# PokerFace.net
KiCad netlist of a schematic drawn in Altium Designer
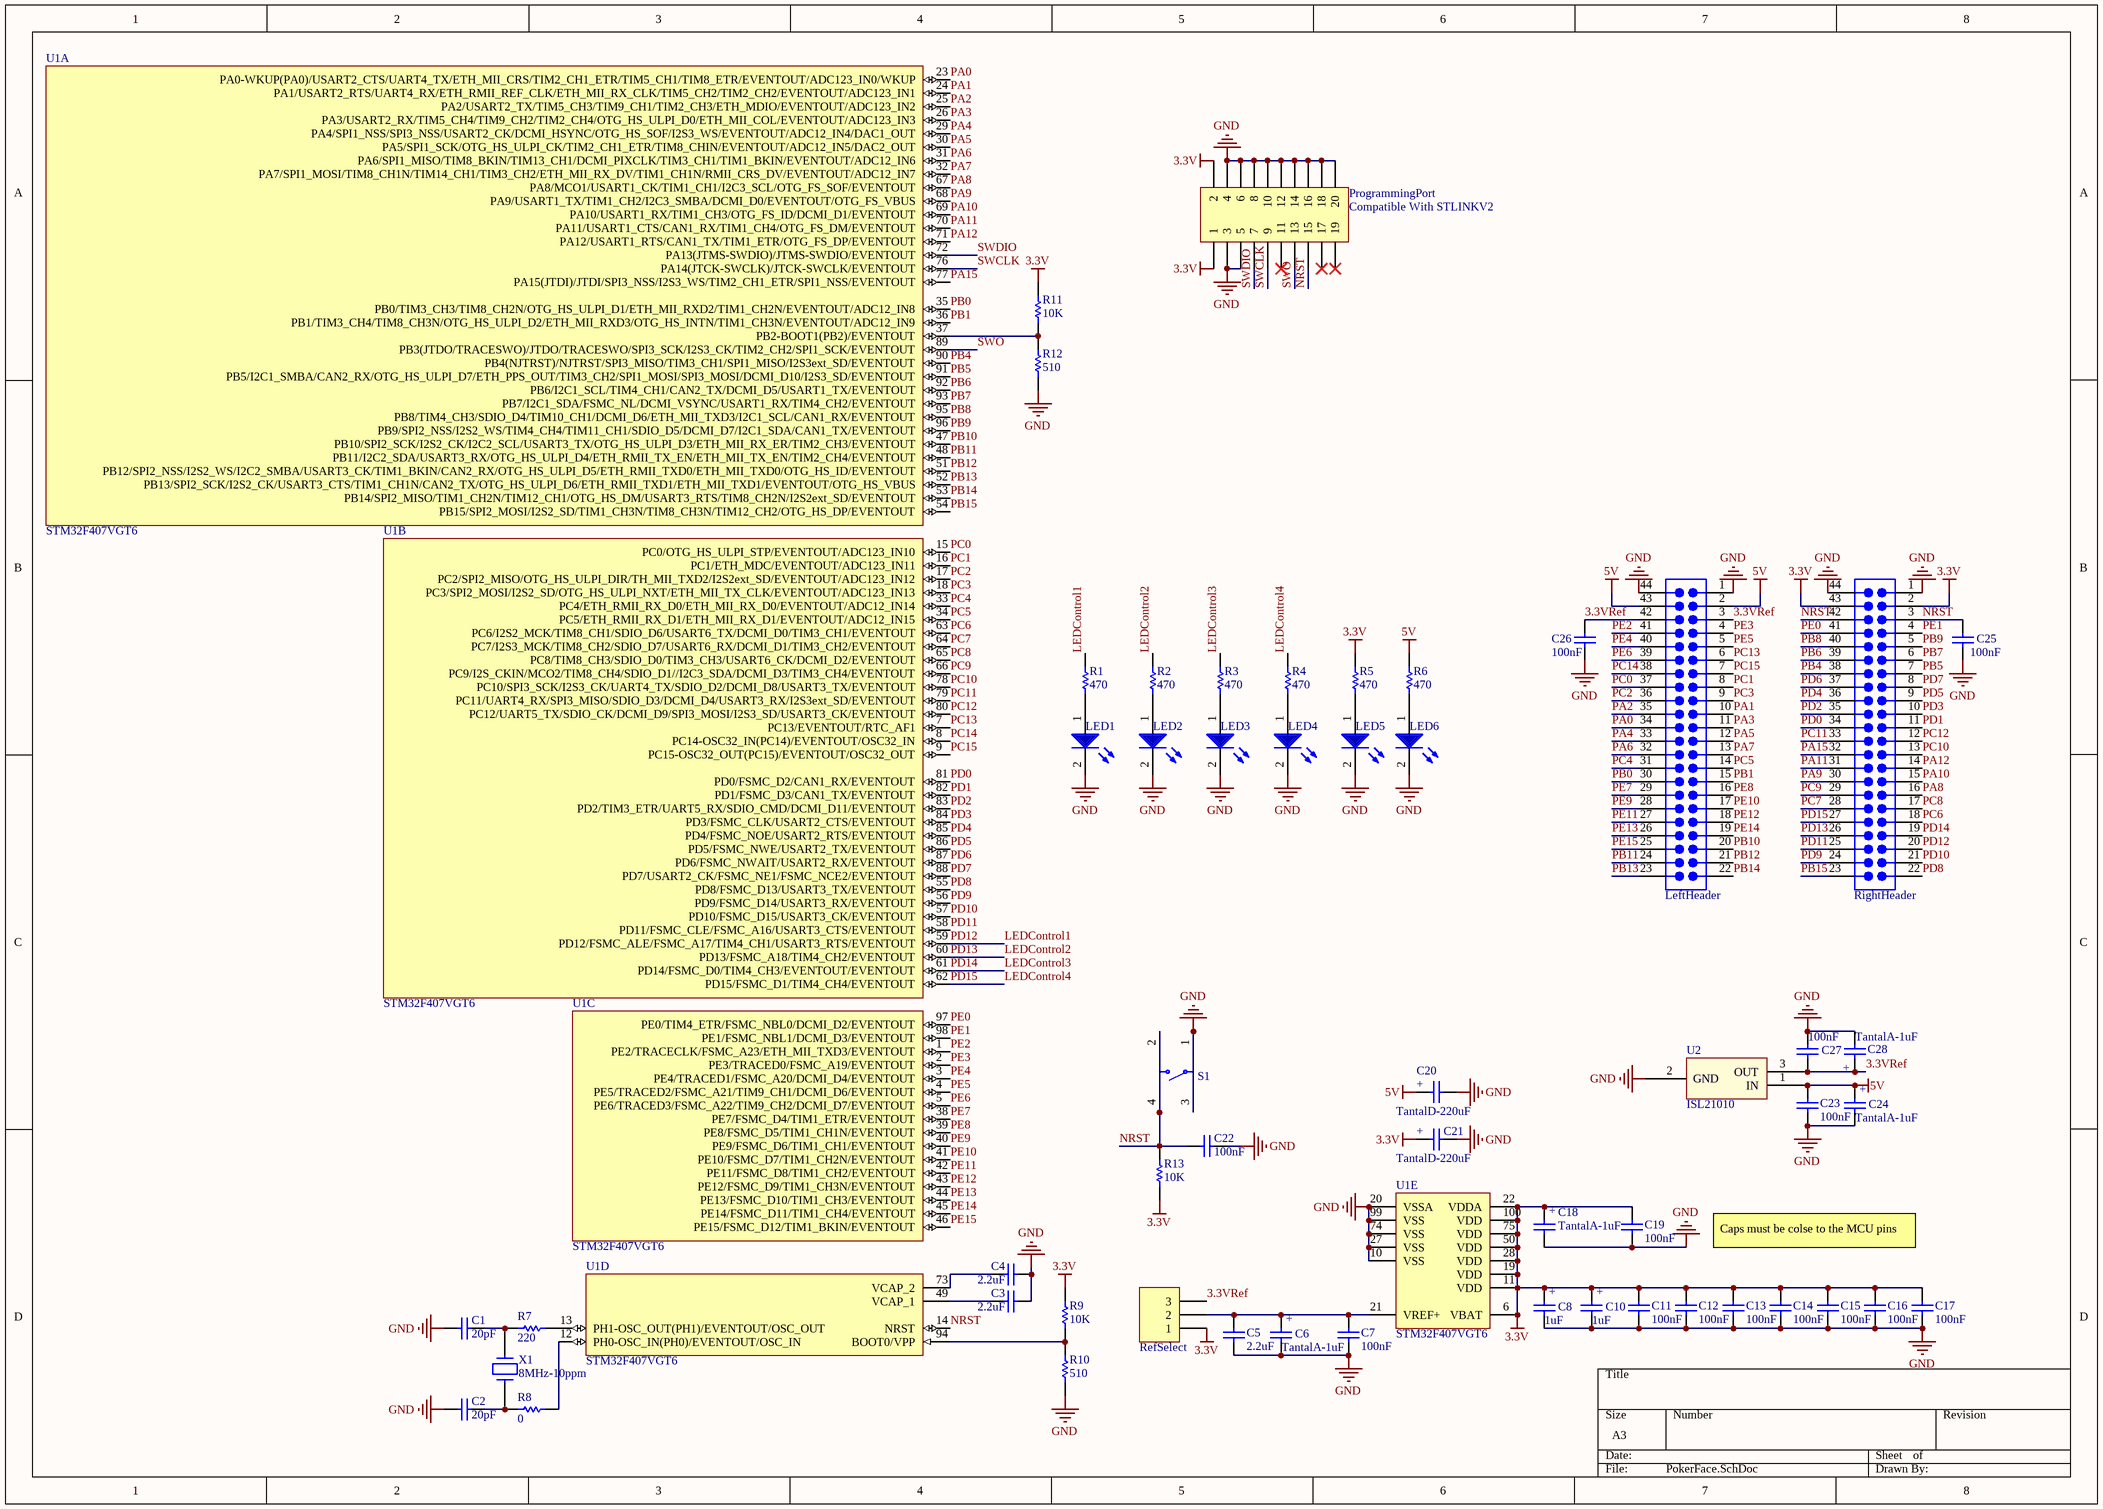
[diagram p0: PokerFace.SchDoc]

(export (version "E")
  (design (tool "Eeschema 10.0.6"))
  (components
    (comp (ref "C1")
      (value "20pF")
      (footprint "SMD 805 CAP")
      (libsource (lib "Aryalib") (part "CAP without Pole"))
    )
    (comp (ref "C2")
      (value "20pF")
      (footprint "SMD 805 CAP")
      (libsource (lib "Aryalib") (part "CAP without Pole"))
    )
    (comp (ref "C3")
      (value "2.2uF")
      (footprint "SMD 805 CAP")
      (libsource (lib "Aryalib") (part "CAP without Pole"))
    )
    (comp (ref "C4")
      (value "2.2uF")
      (footprint "SMD 805 CAP")
      (libsource (lib "Aryalib") (part "CAP without Pole"))
    )
    (comp (ref "C5")
      (value "2.2uF")
      (footprint "SMD 805 CAP")
      (libsource (lib "Aryalib") (part "CAP without Pole"))
    )
    (comp (ref "C6")
      (value "TantalA-1uF")
      (footprint "MY_CAP_SMD-A")
      (description "3.2X1.6MM")
      (libsource (lib "AMINLIB") (part "CAP_TANTAL_A"))
    )
    (comp (ref "C7")
      (value "100nF")
      (footprint "SMD 805 CAP")
      (libsource (lib "Aryalib") (part "CAP without Pole"))
    )
    (comp (ref "C8")
      (value "1uF")
      (footprint "MY_CAP_SMD-A")
      (description "3.2X1.6MM")
      (libsource (lib "AMINLIB") (part "CAP_TANTAL_A"))
    )
    (comp (ref "C10")
      (value "1uF")
      (footprint "MY_CAP_SMD-A")
      (description "3.2X1.6MM")
      (libsource (lib "AMINLIB") (part "CAP_TANTAL_A"))
    )
    (comp (ref "C11")
      (value "100nF")
      (footprint "SMD 805 CAP")
      (libsource (lib "Aryalib") (part "CAP without Pole"))
    )
    (comp (ref "C12")
      (value "100nF")
      (footprint "SMD 805 CAP")
      (libsource (lib "Aryalib") (part "CAP without Pole"))
    )
    (comp (ref "C13")
      (value "100nF")
      (footprint "SMD 805 CAP")
      (libsource (lib "Aryalib") (part "CAP without Pole"))
    )
    (comp (ref "C14")
      (value "100nF")
      (footprint "SMD 805 CAP")
      (libsource (lib "Aryalib") (part "CAP without Pole"))
    )
    (comp (ref "C15")
      (value "100nF")
      (footprint "SMD 805 CAP")
      (libsource (lib "Aryalib") (part "CAP without Pole"))
    )
    (comp (ref "C16")
      (value "100nF")
      (footprint "SMD 805 CAP")
      (libsource (lib "Aryalib") (part "CAP without Pole"))
    )
    (comp (ref "C17")
      (value "100nF")
      (footprint "SMD 805 CAP")
      (libsource (lib "Aryalib") (part "CAP without Pole"))
    )
    (comp (ref "C18")
      (value "TantalA-1uF")
      (footprint "MY_CAP_SMD-A")
      (description "3.2X1.6MM")
      (libsource (lib "AMINLIB") (part "CAP_TANTAL_A"))
    )
    (comp (ref "C19")
      (value "100nF")
      (footprint "SMD 805 CAP")
      (libsource (lib "Aryalib") (part "CAP without Pole"))
    )
    (comp (ref "C20")
      (value "TantalD-220uF")
      (footprint "MY_CAP_SMD-D")
      (description "7.3X4.3MM")
      (libsource (lib "AMINLIB") (part "CAP_TANTAL_D"))
    )
    (comp (ref "C21")
      (value "TantalD-220uF")
      (footprint "MY_CAP_SMD-D")
      (description "7.3X4.3MM")
      (libsource (lib "AMINLIB") (part "CAP_TANTAL_D"))
    )
    (comp (ref "C22")
      (value "100nF")
      (footprint "SMD 805 CAP")
      (libsource (lib "Aryalib") (part "CAP without Pole"))
    )
    (comp (ref "C23")
      (value "100nF")
      (footprint "SMD 805 CAP")
      (libsource (lib "Aryalib") (part "CAP without Pole"))
    )
    (comp (ref "C24")
      (value "TantalA-1uF")
      (footprint "MY_CAP_SMD-A")
      (description "3.2X1.6MM")
      (libsource (lib "AMINLIB") (part "CAP_TANTAL_A"))
    )
    (comp (ref "C25")
      (value "100nF")
      (footprint "SMD 805 CAP")
      (libsource (lib "Aryalib") (part "CAP without Pole"))
    )
    (comp (ref "C26")
      (value "100nF")
      (footprint "SMD 805 CAP")
      (libsource (lib "Aryalib") (part "CAP without Pole"))
    )
    (comp (ref "C27")
      (value "100nF")
      (footprint "SMD 805 CAP")
      (libsource (lib "Aryalib") (part "CAP without Pole"))
    )
    (comp (ref "C28")
      (value "TantalA-1uF")
      (footprint "MY_CAP_SMD-A")
      (description "3.2X1.6MM")
      (libsource (lib "AMINLIB") (part "CAP_TANTAL_A"))
    )
    (comp (ref "LED1")
      (value "150080BS75000")
      (footprint "LED_0805_Blue")
      (description "SMD mono-color Chip LED, WL-SMCW, Blue")
      (fields
        (field (name "MANUFACTURER") "W黵th Elektronik eiSos GmbH")
        (field (name "CREATED BY") "Christin Otto")
      )
      (libsource (lib "WL-SMCW_rev15b") (part "WL-SMCW 0805  150080BS75000"))
    )
    (comp (ref "LED2")
      (value "150080BS75000")
      (footprint "LED_0805_Blue")
      (description "SMD mono-color Chip LED, WL-SMCW, Blue")
      (fields
        (field (name "MANUFACTURER") "W黵th Elektronik eiSos GmbH")
        (field (name "CREATED BY") "Christin Otto")
      )
      (libsource (lib "WL-SMCW_rev15b") (part "WL-SMCW 0805  150080BS75000"))
    )
    (comp (ref "LED3")
      (value "150080BS75000")
      (footprint "LED_0805_Blue")
      (description "SMD mono-color Chip LED, WL-SMCW, Blue")
      (fields
        (field (name "MANUFACTURER") "W黵th Elektronik eiSos GmbH")
        (field (name "CREATED BY") "Christin Otto")
      )
      (libsource (lib "WL-SMCW_rev15b") (part "WL-SMCW 0805  150080BS75000"))
    )
    (comp (ref "LED4")
      (value "150080BS75000")
      (footprint "LED_0805_Blue")
      (description "SMD mono-color Chip LED, WL-SMCW, Blue")
      (fields
        (field (name "MANUFACTURER") "W黵th Elektronik eiSos GmbH")
        (field (name "CREATED BY") "Christin Otto")
      )
      (libsource (lib "WL-SMCW_rev15b") (part "WL-SMCW 0805  150080BS75000"))
    )
    (comp (ref "LED5")
      (value "150080BS75000")
      (footprint "LED_0805_Blue")
      (description "SMD mono-color Chip LED, WL-SMCW, Blue")
      (fields
        (field (name "MANUFACTURER") "W黵th Elektronik eiSos GmbH")
        (field (name "CREATED BY") "Christin Otto")
      )
      (libsource (lib "WL-SMCW_rev15b") (part "WL-SMCW 0805  150080BS75000"))
    )
    (comp (ref "LED6")
      (value "150080BS75000")
      (footprint "LED_0805_Blue")
      (description "SMD mono-color Chip LED, WL-SMCW, Blue")
      (fields
        (field (name "MANUFACTURER") "W黵th Elektronik eiSos GmbH")
        (field (name "CREATED BY") "Christin Otto")
      )
      (libsource (lib "WL-SMCW_rev15b") (part "WL-SMCW 0805  150080BS75000"))
    )
    (comp (ref "LeftHeader")
      (value "WE-2.54 mm Pin Header & Jumper 61304421121")
      (footprint "61304421121")
      (description "WR-PHD 2.54 mm Dual Pin Header")
      (fields
        (field (name "MANUFACTURER") "Würth Elektronik eiSos GmbH")
        (field (name "PARTNO") "61304421121")
        (field (name "CREATED BY") "Karrer Zheng")
      )
      (libsource (lib "WE_WR-PHD_Pin Header_2.54mm_rev15c") (part "WE-2.54 mm Pin Header & Jumper 61304421121"))
    )
    (comp (ref "ProgrammingPort")
      (value "Compatible With STLINKV2")
      (footprint "61202021621")
      (description "WR-BHD 2.54mm Male Box Header")
      (fields
        (field (name "MANUFACTURER") "Würth Elektronik eiSos GmbH")
        (field (name "PARTNO") "61202021621")
        (field (name "CREATED BY") "Karrer Zheng")
      )
      (libsource (lib "WE_WR-BHD_Box Header_2.54mm_rev15b") (part "WE-2,54mm_Box Header 61202021621"))
    )
    (comp (ref "R1") (value "470") (footprint "SMD 805") (libsource (lib "Aryalib") (part "Resistor")))
    (comp (ref "R2") (value "470") (footprint "SMD 805") (libsource (lib "Aryalib") (part "Resistor")))
    (comp (ref "R3") (value "470") (footprint "SMD 805") (libsource (lib "Aryalib") (part "Resistor")))
    (comp (ref "R4") (value "470") (footprint "SMD 805") (libsource (lib "Aryalib") (part "Resistor")))
    (comp (ref "R5") (value "470") (footprint "SMD 805") (libsource (lib "Aryalib") (part "Resistor")))
    (comp (ref "R6") (value "470") (footprint "SMD 805") (libsource (lib "Aryalib") (part "Resistor")))
    (comp (ref "R7") (value "220") (footprint "SMD 805") (libsource (lib "Aryalib") (part "Resistor")))
    (comp (ref "R8") (value "0") (footprint "SMD 805") (libsource (lib "Aryalib") (part "Resistor")))
    (comp (ref "R9") (value "10K") (footprint "SMD 805") (libsource (lib "Aryalib") (part "Resistor")))
    (comp (ref "R10") (value "510") (footprint "SMD 805") (libsource (lib "Aryalib") (part "Resistor")))
    (comp (ref "R11") (value "10K") (footprint "SMD 805") (libsource (lib "Aryalib") (part "Resistor")))
    (comp (ref "R12") (value "510") (footprint "SMD 805") (libsource (lib "Aryalib") (part "Resistor")))
    (comp (ref "R13") (value "10K") (footprint "SMD 805") (libsource (lib "Aryalib") (part "Resistor")))
    (comp (ref "RefSelect")
      (value "WE-2.54 mm Pin Header & Jumper 61300311121")
      (footprint "61300311121")
      (description "WR-PHD 2.54mm Pin Header")
      (fields
        (field (name "MANUFACTURER") "Würth Elektronik eiSos GmbH")
        (field (name "PARTNO") "61300311121")
        (field (name "CREATED BY") "Karrer Zheng")
      )
      (libsource (lib "WE_WR-PHD_Pin Header_2.54mm_rev15c") (part "WE-2.54 mm Pin Header & Jumper 61300311121"))
    )
    (comp (ref "RightHeader")
      (value "WE-2.54 mm Pin Header & Jumper 61304421121")
      (footprint "61304421121")
      (description "WR-PHD 2.54 mm Dual Pin Header")
      (fields
        (field (name "MANUFACTURER") "Würth Elektronik eiSos GmbH")
        (field (name "PARTNO") "61304421121")
        (field (name "CREATED BY") "Karrer Zheng")
      )
      (libsource (lib "WE_WR-PHD_Pin Header_2.54mm_rev15c") (part "WE-2.54 mm Pin Header & Jumper 61304421121"))
    )
    (comp (ref "S1")
      (value "6*6 TactSwitch")
      (footprint "4301x20508x6")
      (description "WS-TASV 6x6 mm SMD")
      (fields
        (field (name "PARTNO") "430152050836")
        (field (name "MANUFACTURER") "Wurth Elektronik")
        (field (name "CREATED BY") "Baojun Chen")
      )
      (libsource (lib "WS-TASV_rev15a") (part "WS-TASV, 430152050836"))
    )
    (comp (ref "U1")
      (value "STM32F407VGT6")
      (footprint "LQFP100_V")
      (libsource (lib "STMicroelectronics STM32 F4") (part "STM32F407VGT6"))
    )
    (comp (ref "U2") (value "ISL21010") (footprint "SOT-23") (libsource (lib "Aryalib") (part "ISL21010")))
    (comp (ref "X1")
      (value "8MHz-10ppm")
      (footprint "My_Crystal")
      (description "Crystal")
      (libsource (lib "AMINLIB") (part "CRYSTAL"))
    )
  )
  (nets
    (net (code "1") (name "/3.3VRef") (class "Default")
      (node (ref "C26") (pin "1") (pinfunction "1_1") (pintype "passive"))
      (node (ref "C27") (pin "2") (pinfunction "2_2") (pintype "passive"))
      (node (ref "C28") (pin "+") (pinfunction "+_+") (pintype "passive"))
      (node (ref "LeftHeader") (pin "3") (pinfunction "3_3") (pintype "passive"))
      (node (ref "LeftHeader") (pin "42") (pinfunction "42_42") (pintype "passive"))
      (node (ref "RefSelect") (pin "3") (pinfunction "3_3") (pintype "passive"))
      (node (ref "U2") (pin "3") (pinfunction "OUT_3") (pintype "passive"))
    )
    (net (code "2") (name "/LEDControl1") (class "Default")
      (node (ref "R1") (pin "2") (pinfunction "2_2") (pintype "passive"))
      (node (ref "RightHeader") (pin "20") (pinfunction "20_20") (pintype "passive"))
      (node (ref "U1") (pin "59") (pinfunction "PD12/FSMC_ALE/FSMC_A17/TIM4_CH1/USART3_RTS/EVENTOUT_59") (pintype "bidirectional"))
    )
    (net (code "3") (name "/LEDControl2") (class "Default")
      (node (ref "R2") (pin "2") (pinfunction "2_2") (pintype "passive"))
      (node (ref "RightHeader") (pin "26") (pinfunction "26_26") (pintype "passive"))
      (node (ref "U1") (pin "60") (pinfunction "PD13/FSMC_A18/TIM4_CH2/EVENTOUT_60") (pintype "bidirectional"))
    )
    (net (code "4") (name "/LEDControl3") (class "Default")
      (node (ref "R3") (pin "2") (pinfunction "2_2") (pintype "passive"))
      (node (ref "RightHeader") (pin "19") (pinfunction "19_19") (pintype "passive"))
      (node (ref "U1") (pin "61") (pinfunction "PD14/FSMC_D0/TIM4_CH3/EVENTOUT/EVENTOUT_61") (pintype "bidirectional"))
    )
    (net (code "5") (name "/LEDControl4") (class "Default")
      (node (ref "R4") (pin "2") (pinfunction "2_2") (pintype "passive"))
      (node (ref "RightHeader") (pin "27") (pinfunction "27_27") (pintype "passive"))
      (node (ref "U1") (pin "62") (pinfunction "PD15/FSMC_D1/TIM4_CH4/EVENTOUT_62") (pintype "bidirectional"))
    )
    (net (code "6") (name "/NRST") (class "Default")
      (node (ref "C22") (pin "2") (pinfunction "2_2") (pintype "passive"))
      (node (ref "C25") (pin "1") (pinfunction "1_1") (pintype "passive"))
      (node (ref "ProgrammingPort") (pin "15") (pinfunction "15_15") (pintype "passive"))
      (node (ref "R13") (pin "2") (pinfunction "2_2") (pintype "passive"))
      (node (ref "RightHeader") (pin "3") (pinfunction "3_3") (pintype "passive"))
      (node (ref "RightHeader") (pin "42") (pinfunction "42_42") (pintype "passive"))
      (node (ref "S1") (pin "2") (pinfunction "2_2") (pintype "passive"))
      (node (ref "S1") (pin "4") (pinfunction "4_4") (pintype "passive"))
      (node (ref "U1") (pin "14") (pinfunction "NRST_14") (pintype "bidirectional"))
    )
    (net (code "7") (name "/PA0") (class "Default")
      (node (ref "LeftHeader") (pin "34") (pinfunction "34_34") (pintype "passive"))
      (node (ref "U1") (pin "23") (pinfunction "PA0-WKUP(PA0)/USART2_CTS/UART4_TX/ETH_MII_CRS/TIM2_CH1_ETR/TIM5_CH1/TIM8_ETR/EVENTOUT/ADC123_IN0/WKUP_23") (pintype "bidirectional"))
    )
    (net (code "8") (name "/PA1") (class "Default")
      (node (ref "LeftHeader") (pin "10") (pinfunction "10_10") (pintype "passive"))
      (node (ref "U1") (pin "24") (pinfunction "PA1/USART2_RTS/UART4_RX/ETH_RMII_REF_CLK/ETH_MII_RX_CLK/TIM5_CH2/TIM2_CH2/EVENTOUT/ADC123_IN1_24") (pintype "bidirectional"))
    )
    (net (code "9") (name "/PA2") (class "Default")
      (node (ref "LeftHeader") (pin "35") (pinfunction "35_35") (pintype "passive"))
      (node (ref "U1") (pin "25") (pinfunction "PA2/USART2_TX/TIM5_CH3/TIM9_CH1/TIM2_CH3/ETH_MDIO/EVENTOUT/ADC123_IN2_25") (pintype "bidirectional"))
    )
    (net (code "10") (name "/PA3") (class "Default")
      (node (ref "LeftHeader") (pin "11") (pinfunction "11_11") (pintype "passive"))
      (node (ref "U1") (pin "26") (pinfunction "PA3/USART2_RX/TIM5_CH4/TIM9_CH2/TIM2_CH4/OTG_HS_ULPI_D0/ETH_MII_COL/EVENTOUT/ADC123_IN3_26") (pintype "bidirectional"))
    )
    (net (code "11") (name "/PA4") (class "Default")
      (node (ref "LeftHeader") (pin "33") (pinfunction "33_33") (pintype "passive"))
      (node (ref "U1") (pin "29") (pinfunction "PA4/SPI1_NSS/SPI3_NSS/USART2_CK/DCMI_HSYNC/OTG_HS_SOF/I2S3_WS/EVENTOUT/ADC12_IN4/DAC1_OUT_29") (pintype "bidirectional"))
    )
    (net (code "12") (name "/PA5") (class "Default")
      (node (ref "LeftHeader") (pin "12") (pinfunction "12_12") (pintype "passive"))
      (node (ref "U1") (pin "30") (pinfunction "PA5/SPI1_SCK/OTG_HS_ULPI_CK/TIM2_CH1_ETR/TIM8_CHIN/EVENTOUT/ADC12_IN5/DAC2_OUT_30") (pintype "bidirectional"))
    )
    (net (code "13") (name "/PA6") (class "Default")
      (node (ref "LeftHeader") (pin "32") (pinfunction "32_32") (pintype "passive"))
      (node (ref "U1") (pin "31") (pinfunction "PA6/SPI1_MISO/TIM8_BKIN/TIM13_CH1/DCMI_PIXCLK/TIM3_CH1/TIM1_BKIN/EVENTOUT/ADC12_IN6_31") (pintype "bidirectional"))
    )
    (net (code "14") (name "/PA7") (class "Default")
      (node (ref "LeftHeader") (pin "13") (pinfunction "13_13") (pintype "passive"))
      (node (ref "U1") (pin "32") (pinfunction "PA7/SPI1_MOSI/TIM8_CH1N/TIM14_CH1/TIM3_CH2/ETH_MII_RX_DV/TIM1_CH1N/RMII_CRS_DV/EVENTOUT/ADC12_IN7_32") (pintype "bidirectional"))
    )
    (net (code "15") (name "/PA8") (class "Default")
      (node (ref "RightHeader") (pin "16") (pinfunction "16_16") (pintype "passive"))
      (node (ref "U1") (pin "67") (pinfunction "PA8/MCO1/USART1_CK/TIM1_CH1/I2C3_SCL/OTG_FS_SOF/EVENTOUT_67") (pintype "bidirectional"))
    )
    (net (code "16") (name "/PA9") (class "Default")
      (node (ref "RightHeader") (pin "30") (pinfunction "30_30") (pintype "passive"))
      (node (ref "U1") (pin "68") (pinfunction "PA9/USART1_TX/TIM1_CH2/I2C3_SMBA/DCMI_D0/EVENTOUT/OTG_FS_VBUS_68") (pintype "bidirectional"))
    )
    (net (code "17") (name "/PA10") (class "Default")
      (node (ref "RightHeader") (pin "15") (pinfunction "15_15") (pintype "passive"))
      (node (ref "U1") (pin "69") (pinfunction "PA10/USART1_RX/TIM1_CH3/OTG_FS_ID/DCMI_D1/EVENTOUT_69") (pintype "bidirectional"))
    )
    (net (code "18") (name "/PA11") (class "Default")
      (node (ref "RightHeader") (pin "31") (pinfunction "31_31") (pintype "passive"))
      (node (ref "U1") (pin "70") (pinfunction "PA11/USART1_CTS/CAN1_RX/TIM1_CH4/OTG_FS_DM/EVENTOUT_70") (pintype "bidirectional"))
    )
    (net (code "19") (name "/PA12") (class "Default")
      (node (ref "RightHeader") (pin "14") (pinfunction "14_14") (pintype "passive"))
      (node (ref "U1") (pin "71") (pinfunction "PA12/USART1_RTS/CAN1_TX/TIM1_ETR/OTG_FS_DP/EVENTOUT_71") (pintype "bidirectional"))
    )
    (net (code "20") (name "/PA15") (class "Default")
      (node (ref "RightHeader") (pin "32") (pinfunction "32_32") (pintype "passive"))
      (node (ref "U1") (pin "77") (pinfunction "PA15(JTDI)/JTDI/SPI3_NSS/I2S3_WS/TIM2_CH1_ETR/SPI1_NSS/EVENTOUT_77") (pintype "bidirectional"))
    )
    (net (code "21") (name "/PB0") (class "Default")
      (node (ref "LeftHeader") (pin "30") (pinfunction "30_30") (pintype "passive"))
      (node (ref "U1") (pin "35") (pinfunction "PB0/TIM3_CH3/TIM8_CH2N/OTG_HS_ULPI_D1/ETH_MII_RXD2/TIM1_CH2N/EVENTOUT/ADC12_IN8_35") (pintype "bidirectional"))
    )
    (net (code "22") (name "/PB1") (class "Default")
      (node (ref "LeftHeader") (pin "15") (pinfunction "15_15") (pintype "passive"))
      (node (ref "U1") (pin "36") (pinfunction "PB1/TIM3_CH4/TIM8_CH3N/OTG_HS_ULPI_D2/ETH_MII_RXD3/OTG_HS_INTN/TIM1_CH3N/EVENTOUT/ADC12_IN9_36") (pintype "bidirectional"))
    )
    (net (code "23") (name "/PB4") (class "Default")
      (node (ref "RightHeader") (pin "38") (pinfunction "38_38") (pintype "passive"))
      (node (ref "U1") (pin "90") (pinfunction "PB4(NJTRST)/NJTRST/SPI3_MISO/TIM3_CH1/SPI1_MISO/I2S3ext_SD/EVENTOUT_90") (pintype "bidirectional"))
    )
    (net (code "24") (name "/PB5") (class "Default")
      (node (ref "RightHeader") (pin "7") (pinfunction "7_7") (pintype "passive"))
      (node (ref "U1") (pin "91") (pinfunction "PB5/I2C1_SMBA/CAN2_RX/OTG_HS_ULPI_D7/ETH_PPS_OUT/TIM3_CH2/SPI1_MOSI/SPI3_MOSI/DCMI_D10/I2S3_SD/EVENTOUT_91") (pintype "bidirectional"))
    )
    (net (code "25") (name "/PB6") (class "Default")
      (node (ref "RightHeader") (pin "39") (pinfunction "39_39") (pintype "passive"))
      (node (ref "U1") (pin "92") (pinfunction "PB6/I2C1_SCL/TIM4_CH1/CAN2_TX/DCMI_D5/USART1_TX/EVENTOUT_92") (pintype "bidirectional"))
    )
    (net (code "26") (name "/PB7") (class "Default")
      (node (ref "RightHeader") (pin "6") (pinfunction "6_6") (pintype "passive"))
      (node (ref "U1") (pin "93") (pinfunction "PB7/I2C1_SDA/FSMC_NL/DCMI_VSYNC/USART1_RX/TIM4_CH2/EVENTOUT_93") (pintype "bidirectional"))
    )
    (net (code "27") (name "/PB8") (class "Default")
      (node (ref "RightHeader") (pin "40") (pinfunction "40_40") (pintype "passive"))
      (node (ref "U1") (pin "95") (pinfunction "PB8/TIM4_CH3/SDIO_D4/TIM10_CH1/DCMI_D6/ETH_MII_TXD3/I2C1_SCL/CAN1_RX/EVENTOUT_95") (pintype "bidirectional"))
    )
    (net (code "28") (name "/PB9") (class "Default")
      (node (ref "RightHeader") (pin "5") (pinfunction "5_5") (pintype "passive"))
      (node (ref "U1") (pin "96") (pinfunction "PB9/SPI2_NSS/I2S2_WS/TIM4_CH4/TIM11_CH1/SDIO_D5/DCMI_D7/I2C1_SDA/CAN1_TX/EVENTOUT_96") (pintype "bidirectional"))
    )
    (net (code "29") (name "/PB10") (class "Default")
      (node (ref "LeftHeader") (pin "20") (pinfunction "20_20") (pintype "passive"))
      (node (ref "U1") (pin "47") (pinfunction "PB10/SPI2_SCK/I2S2_CK/I2C2_SCL/USART3_TX/OTG_HS_ULPI_D3/ETH_MII_RX_ER/TIM2_CH3/EVENTOUT_47") (pintype "bidirectional"))
    )
    (net (code "30") (name "/PB11") (class "Default")
      (node (ref "LeftHeader") (pin "24") (pinfunction "24_24") (pintype "passive"))
      (node (ref "U1") (pin "48") (pinfunction "PB11/I2C2_SDA/USART3_RX/OTG_HS_ULPI_D4/ETH_RMII_TX_EN/ETH_MII_TX_EN/TIM2_CH4/EVENTOUT_48") (pintype "bidirectional"))
    )
    (net (code "31") (name "/PB12") (class "Default")
      (node (ref "LeftHeader") (pin "21") (pinfunction "21_21") (pintype "passive"))
      (node (ref "U1") (pin "51") (pinfunction "PB12/SPI2_NSS/I2S2_WS/I2C2_SMBA/USART3_CK/TIM1_BKIN/CAN2_RX/OTG_HS_ULPI_D5/ETH_RMII_TXD0/ETH_MII_TXD0/OTG_HS_ID/EVENTOUT_51") (pintype "bidirectional"))
    )
    (net (code "32") (name "/PB13") (class "Default")
      (node (ref "LeftHeader") (pin "23") (pinfunction "23_23") (pintype "passive"))
      (node (ref "U1") (pin "52") (pinfunction "PB13/SPI2_SCK/I2S2_CK/USART3_CTS/TIM1_CH1N/CAN2_TX/OTG_HS_ULPI_D6/ETH_RMII_TXD1/ETH_MII_TXD1/EVENTOUT/OTG_HS_VBUS_52") (pintype "bidirectional"))
    )
    (net (code "33") (name "/PB14") (class "Default")
      (node (ref "LeftHeader") (pin "22") (pinfunction "22_22") (pintype "passive"))
      (node (ref "U1") (pin "53") (pinfunction "PB14/SPI2_MISO/TIM1_CH2N/TIM12_CH1/OTG_HS_DM/USART3_RTS/TIM8_CH2N/I2S2ext_SD/EVENTOUT_53") (pintype "bidirectional"))
    )
    (net (code "34") (name "/PB15") (class "Default")
      (node (ref "RightHeader") (pin "23") (pinfunction "23_23") (pintype "passive"))
      (node (ref "U1") (pin "54") (pinfunction "PB15/SPI2_MOSI/I2S2_SD/TIM1_CH3N/TIM8_CH3N/TIM12_CH2/OTG_HS_DP/EVENTOUT_54") (pintype "bidirectional"))
    )
    (net (code "35") (name "/PC0") (class "Default")
      (node (ref "LeftHeader") (pin "37") (pinfunction "37_37") (pintype "passive"))
      (node (ref "U1") (pin "15") (pinfunction "PC0/OTG_HS_ULPI_STP/EVENTOUT/ADC123_IN10_15") (pintype "bidirectional"))
    )
    (net (code "36") (name "/PC1") (class "Default")
      (node (ref "LeftHeader") (pin "8") (pinfunction "8_8") (pintype "passive"))
      (node (ref "U1") (pin "16") (pinfunction "PC1/ETH_MDC/EVENTOUT/ADC123_IN11_16") (pintype "bidirectional"))
    )
    (net (code "37") (name "/PC2") (class "Default")
      (node (ref "LeftHeader") (pin "36") (pinfunction "36_36") (pintype "passive"))
      (node (ref "U1") (pin "17") (pinfunction "PC2/SPI2_MISO/OTG_HS_ULPI_DIR/TH_MII_TXD2/I2S2ext_SD/EVENTOUT/ADC123_IN12_17") (pintype "bidirectional"))
    )
    (net (code "38") (name "/PC3") (class "Default")
      (node (ref "LeftHeader") (pin "9") (pinfunction "9_9") (pintype "passive"))
      (node (ref "U1") (pin "18") (pinfunction "PC3/SPI2_MOSI/I2S2_SD/OTG_HS_ULPI_NXT/ETH_MII_TX_CLK/EVENTOUT/ADC123_IN13_18") (pintype "bidirectional"))
    )
    (net (code "39") (name "/PC4") (class "Default")
      (node (ref "LeftHeader") (pin "31") (pinfunction "31_31") (pintype "passive"))
      (node (ref "U1") (pin "33") (pinfunction "PC4/ETH_RMII_RX_D0/ETH_MII_RX_D0/EVENTOUT/ADC12_IN14_33") (pintype "bidirectional"))
    )
    (net (code "40") (name "/PC5") (class "Default")
      (node (ref "LeftHeader") (pin "14") (pinfunction "14_14") (pintype "passive"))
      (node (ref "U1") (pin "34") (pinfunction "PC5/ETH_RMII_RX_D1/ETH_MII_RX_D1/EVENTOUT/ADC12_IN15_34") (pintype "bidirectional"))
    )
    (net (code "41") (name "/PC6") (class "Default")
      (node (ref "RightHeader") (pin "18") (pinfunction "18_18") (pintype "passive"))
      (node (ref "U1") (pin "63") (pinfunction "PC6/I2S2_MCK/TIM8_CH1/SDIO_D6/USART6_TX/DCMI_D0/TIM3_CH1/EVENTOUT_63") (pintype "bidirectional"))
    )
    (net (code "42") (name "/PC7") (class "Default")
      (node (ref "RightHeader") (pin "28") (pinfunction "28_28") (pintype "passive"))
      (node (ref "U1") (pin "64") (pinfunction "PC7/I2S3_MCK/TIM8_CH2/SDIO_D7/USART6_RX/DCMI_D1/TIM3_CH2/EVENTOUT_64") (pintype "bidirectional"))
    )
    (net (code "43") (name "/PC8") (class "Default")
      (node (ref "RightHeader") (pin "17") (pinfunction "17_17") (pintype "passive"))
      (node (ref "U1") (pin "65") (pinfunction "PC8/TIM8_CH3/SDIO_D0/TIM3_CH3/USART6_CK/DCMI_D2/EVENTOUT_65") (pintype "bidirectional"))
    )
    (net (code "44") (name "/PC9") (class "Default")
      (node (ref "RightHeader") (pin "29") (pinfunction "29_29") (pintype "passive"))
      (node (ref "U1") (pin "66") (pinfunction "PC9/I2S_CKIN/MCO2/TIM8_CH4/SDIO_D1//I2C3_SDA/DCMI_D3/TIM3_CH4/EVENTOUT_66") (pintype "bidirectional"))
    )
    (net (code "45") (name "/PC10") (class "Default")
      (node (ref "RightHeader") (pin "13") (pinfunction "13_13") (pintype "passive"))
      (node (ref "U1") (pin "78") (pinfunction "PC10/SPI3_SCK/I2S3_CK/UART4_TX/SDIO_D2/DCMI_D8/USART3_TX/EVENTOUT_78") (pintype "bidirectional"))
    )
    (net (code "46") (name "/PC11") (class "Default")
      (node (ref "RightHeader") (pin "33") (pinfunction "33_33") (pintype "passive"))
      (node (ref "U1") (pin "79") (pinfunction "PC11/UART4_RX/SPI3_MISO/SDIO_D3/DCMI_D4/USART3_RX/I2S3ext_SD/EVENTOUT_79") (pintype "bidirectional"))
    )
    (net (code "47") (name "/PC12") (class "Default")
      (node (ref "RightHeader") (pin "12") (pinfunction "12_12") (pintype "passive"))
      (node (ref "U1") (pin "80") (pinfunction "PC12/UART5_TX/SDIO_CK/DCMI_D9/SPI3_MOSI/I2S3_SD/USART3_CK/EVENTOUT_80") (pintype "bidirectional"))
    )
    (net (code "48") (name "/PC13") (class "Default")
      (node (ref "LeftHeader") (pin "6") (pinfunction "6_6") (pintype "passive"))
      (node (ref "U1") (pin "7") (pinfunction "PC13/EVENTOUT/RTC_AF1_7") (pintype "bidirectional"))
    )
    (net (code "49") (name "/PC14") (class "Default")
      (node (ref "LeftHeader") (pin "38") (pinfunction "38_38") (pintype "passive"))
      (node (ref "U1") (pin "8") (pinfunction "PC14-OSC32_IN(PC14)/EVENTOUT/OSC32_IN_8") (pintype "bidirectional"))
    )
    (net (code "50") (name "/PC15") (class "Default")
      (node (ref "LeftHeader") (pin "7") (pinfunction "7_7") (pintype "passive"))
      (node (ref "U1") (pin "9") (pinfunction "PC15-OSC32_OUT(PC15)/EVENTOUT/OSC32_OUT_9") (pintype "bidirectional"))
    )
    (net (code "51") (name "/PD0") (class "Default")
      (node (ref "RightHeader") (pin "34") (pinfunction "34_34") (pintype "passive"))
      (node (ref "U1") (pin "81") (pinfunction "PD0/FSMC_D2/CAN1_RX/EVENTOUT_81") (pintype "bidirectional"))
    )
    (net (code "52") (name "/PD1") (class "Default")
      (node (ref "RightHeader") (pin "11") (pinfunction "11_11") (pintype "passive"))
      (node (ref "U1") (pin "82") (pinfunction "PD1/FSMC_D3/CAN1_TX/EVENTOUT_82") (pintype "bidirectional"))
    )
    (net (code "53") (name "/PD2") (class "Default")
      (node (ref "RightHeader") (pin "35") (pinfunction "35_35") (pintype "passive"))
      (node (ref "U1") (pin "83") (pinfunction "PD2/TIM3_ETR/UART5_RX/SDIO_CMD/DCMI_D11/EVENTOUT_83") (pintype "bidirectional"))
    )
    (net (code "54") (name "/PD3") (class "Default")
      (node (ref "RightHeader") (pin "10") (pinfunction "10_10") (pintype "passive"))
      (node (ref "U1") (pin "84") (pinfunction "PD3/FSMC_CLK/USART2_CTS/EVENTOUT_84") (pintype "bidirectional"))
    )
    (net (code "55") (name "/PD4") (class "Default")
      (node (ref "RightHeader") (pin "36") (pinfunction "36_36") (pintype "passive"))
      (node (ref "U1") (pin "85") (pinfunction "PD4/FSMC_NOE/USART2_RTS/EVENTOUT_85") (pintype "bidirectional"))
    )
    (net (code "56") (name "/PD5") (class "Default")
      (node (ref "RightHeader") (pin "9") (pinfunction "9_9") (pintype "passive"))
      (node (ref "U1") (pin "86") (pinfunction "PD5/FSMC_NWE/USART2_TX/EVENTOUT_86") (pintype "bidirectional"))
    )
    (net (code "57") (name "/PD6") (class "Default")
      (node (ref "RightHeader") (pin "37") (pinfunction "37_37") (pintype "passive"))
      (node (ref "U1") (pin "87") (pinfunction "PD6/FSMC_NWAIT/USART2_RX/EVENTOUT_87") (pintype "bidirectional"))
    )
    (net (code "58") (name "/PD7") (class "Default")
      (node (ref "RightHeader") (pin "8") (pinfunction "8_8") (pintype "passive"))
      (node (ref "U1") (pin "88") (pinfunction "PD7/USART2_CK/FSMC_NE1/FSMC_NCE2/EVENTOUT_88") (pintype "bidirectional"))
    )
    (net (code "59") (name "/PD8") (class "Default")
      (node (ref "RightHeader") (pin "22") (pinfunction "22_22") (pintype "passive"))
      (node (ref "U1") (pin "55") (pinfunction "PD8/FSMC_D13/USART3_TX/EVENTOUT_55") (pintype "bidirectional"))
    )
    (net (code "60") (name "/PD9") (class "Default")
      (node (ref "RightHeader") (pin "24") (pinfunction "24_24") (pintype "passive"))
      (node (ref "U1") (pin "56") (pinfunction "PD9/FSMC_D14/USART3_RX/EVENTOUT_56") (pintype "bidirectional"))
    )
    (net (code "61") (name "/PD10") (class "Default")
      (node (ref "RightHeader") (pin "21") (pinfunction "21_21") (pintype "passive"))
      (node (ref "U1") (pin "57") (pinfunction "PD10/FSMC_D15/USART3_CK/EVENTOUT_57") (pintype "bidirectional"))
    )
    (net (code "62") (name "/PD11") (class "Default")
      (node (ref "RightHeader") (pin "25") (pinfunction "25_25") (pintype "passive"))
      (node (ref "U1") (pin "58") (pinfunction "PD11/FSMC_CLE/FSMC_A16/USART3_CTS/EVENTOUT_58") (pintype "bidirectional"))
    )
    (net (code "63") (name "/PE0") (class "Default")
      (node (ref "RightHeader") (pin "41") (pinfunction "41_41") (pintype "passive"))
      (node (ref "U1") (pin "97") (pinfunction "PE0/TIM4_ETR/FSMC_NBL0/DCMI_D2/EVENTOUT_97") (pintype "bidirectional"))
    )
    (net (code "64") (name "/PE1") (class "Default")
      (node (ref "RightHeader") (pin "4") (pinfunction "4_4") (pintype "passive"))
      (node (ref "U1") (pin "98") (pinfunction "PE1/FSMC_NBL1/DCMI_D3/EVENTOUT_98") (pintype "bidirectional"))
    )
    (net (code "65") (name "/PE2") (class "Default")
      (node (ref "LeftHeader") (pin "41") (pinfunction "41_41") (pintype "passive"))
      (node (ref "U1") (pin "1") (pinfunction "PE2/TRACECLK/FSMC_A23/ETH_MII_TXD3/EVENTOUT_1") (pintype "bidirectional"))
    )
    (net (code "66") (name "/PE3") (class "Default")
      (node (ref "LeftHeader") (pin "4") (pinfunction "4_4") (pintype "passive"))
      (node (ref "U1") (pin "2") (pinfunction "PE3/TRACED0/FSMC_A19/EVENTOUT_2") (pintype "bidirectional"))
    )
    (net (code "67") (name "/PE4") (class "Default")
      (node (ref "LeftHeader") (pin "40") (pinfunction "40_40") (pintype "passive"))
      (node (ref "U1") (pin "3") (pinfunction "PE4/TRACED1/FSMC_A20/DCMI_D4/EVENTOUT_3") (pintype "bidirectional"))
    )
    (net (code "68") (name "/PE5") (class "Default")
      (node (ref "LeftHeader") (pin "5") (pinfunction "5_5") (pintype "passive"))
      (node (ref "U1") (pin "4") (pinfunction "PE5/TRACED2/FSMC_A21/TIM9_CH1/DCMI_D6/EVENTOUT_4") (pintype "bidirectional"))
    )
    (net (code "69") (name "/PE6") (class "Default")
      (node (ref "LeftHeader") (pin "39") (pinfunction "39_39") (pintype "passive"))
      (node (ref "U1") (pin "5") (pinfunction "PE6/TRACED3/FSMC_A22/TIM9_CH2/DCMI_D7/EVENTOUT_5") (pintype "bidirectional"))
    )
    (net (code "70") (name "/PE7") (class "Default")
      (node (ref "LeftHeader") (pin "29") (pinfunction "29_29") (pintype "passive"))
      (node (ref "U1") (pin "38") (pinfunction "PE7/FSMC_D4/TIM1_ETR/EVENTOUT_38") (pintype "bidirectional"))
    )
    (net (code "71") (name "/PE8") (class "Default")
      (node (ref "LeftHeader") (pin "16") (pinfunction "16_16") (pintype "passive"))
      (node (ref "U1") (pin "39") (pinfunction "PE8/FSMC_D5/TIM1_CH1N/EVENTOUT_39") (pintype "bidirectional"))
    )
    (net (code "72") (name "/PE9") (class "Default")
      (node (ref "LeftHeader") (pin "28") (pinfunction "28_28") (pintype "passive"))
      (node (ref "U1") (pin "40") (pinfunction "PE9/FSMC_D6/TIM1_CH1/EVENTOUT_40") (pintype "bidirectional"))
    )
    (net (code "73") (name "/PE10") (class "Default")
      (node (ref "LeftHeader") (pin "17") (pinfunction "17_17") (pintype "passive"))
      (node (ref "U1") (pin "41") (pinfunction "PE10/FSMC_D7/TIM1_CH2N/EVENTOUT_41") (pintype "bidirectional"))
    )
    (net (code "74") (name "/PE11") (class "Default")
      (node (ref "LeftHeader") (pin "27") (pinfunction "27_27") (pintype "passive"))
      (node (ref "U1") (pin "42") (pinfunction "PE11/FSMC_D8/TIM1_CH2/EVENTOUT_42") (pintype "bidirectional"))
    )
    (net (code "75") (name "/PE12") (class "Default")
      (node (ref "LeftHeader") (pin "18") (pinfunction "18_18") (pintype "passive"))
      (node (ref "U1") (pin "43") (pinfunction "PE12/FSMC_D9/TIM1_CH3N/EVENTOUT_43") (pintype "bidirectional"))
    )
    (net (code "76") (name "/PE13") (class "Default")
      (node (ref "LeftHeader") (pin "26") (pinfunction "26_26") (pintype "passive"))
      (node (ref "U1") (pin "44") (pinfunction "PE13/FSMC_D10/TIM1_CH3/EVENTOUT_44") (pintype "bidirectional"))
    )
    (net (code "77") (name "/PE14") (class "Default")
      (node (ref "LeftHeader") (pin "19") (pinfunction "19_19") (pintype "passive"))
      (node (ref "U1") (pin "45") (pinfunction "PE14/FSMC_D11/TIM1_CH4/EVENTOUT_45") (pintype "bidirectional"))
    )
    (net (code "78") (name "/PE15") (class "Default")
      (node (ref "LeftHeader") (pin "25") (pinfunction "25_25") (pintype "passive"))
      (node (ref "U1") (pin "46") (pinfunction "PE15/FSMC_D12/TIM1_BKIN/EVENTOUT_46") (pintype "bidirectional"))
    )
    (net (code "79") (name "/SWCLK") (class "Default")
      (node (ref "ProgrammingPort") (pin "9") (pinfunction "9_9") (pintype "passive"))
      (node (ref "U1") (pin "76") (pinfunction "PA14(JTCK-SWCLK)/JTCK-SWCLK/EVENTOUT_76") (pintype "bidirectional"))
    )
    (net (code "80") (name "/SWDIO") (class "Default")
      (node (ref "ProgrammingPort") (pin "7") (pinfunction "7_7") (pintype "passive"))
      (node (ref "U1") (pin "72") (pinfunction "PA13(JTMS-SWDIO)/JTMS-SWDIO/EVENTOUT_72") (pintype "bidirectional"))
    )
    (net (code "81") (name "/SWO") (class "Default")
      (node (ref "ProgrammingPort") (pin "13") (pinfunction "13_13") (pintype "passive"))
      (node (ref "U1") (pin "89") (pinfunction "PB3(JTDO/TRACESWO)/JTDO/TRACESWO/SPI3_SCK/I2S3_CK/TIM2_CH2/SPI1_SCK/EVENTOUT_89") (pintype "bidirectional"))
    )
    (net (code "82") (name "3.3V") (class "Default")
      (node (ref "C10") (pin "+") (pinfunction "+_+") (pintype "passive"))
      (node (ref "C11") (pin "1") (pinfunction "1_1") (pintype "passive"))
      (node (ref "C12") (pin "1") (pinfunction "1_1") (pintype "passive"))
      (node (ref "C13") (pin "1") (pinfunction "1_1") (pintype "passive"))
      (node (ref "C14") (pin "1") (pinfunction "1_1") (pintype "passive"))
      (node (ref "C15") (pin "1") (pinfunction "1_1") (pintype "passive"))
      (node (ref "C16") (pin "1") (pinfunction "1_1") (pintype "passive"))
      (node (ref "C17") (pin "1") (pinfunction "1_1") (pintype "passive"))
      (node (ref "C18") (pin "+") (pinfunction "+_+") (pintype "passive"))
      (node (ref "C19") (pin "1") (pinfunction "1_1") (pintype "passive"))
      (node (ref "C21") (pin "+") (pinfunction "+_+") (pintype "passive"))
      (node (ref "C8") (pin "+") (pinfunction "+_+") (pintype "passive"))
      (node (ref "ProgrammingPort") (pin "1") (pinfunction "1_1") (pintype "passive"))
      (node (ref "ProgrammingPort") (pin "2") (pinfunction "2_2") (pintype "passive"))
      (node (ref "R11") (pin "2") (pinfunction "2_2") (pintype "passive"))
      (node (ref "R13") (pin "1") (pinfunction "1_1") (pintype "passive"))
      (node (ref "R5") (pin "2") (pinfunction "2_2") (pintype "passive"))
      (node (ref "R9") (pin "2") (pinfunction "2_2") (pintype "passive"))
      (node (ref "RefSelect") (pin "1") (pinfunction "1_1") (pintype "passive"))
      (node (ref "RightHeader") (pin "2") (pinfunction "2_2") (pintype "passive"))
      (node (ref "RightHeader") (pin "43") (pinfunction "43_43") (pintype "passive"))
      (node (ref "U1") (pin "100") (pinfunction "VDD_100") (pintype "power_in"))
      (node (ref "U1") (pin "11") (pinfunction "VDD_11") (pintype "power_in"))
      (node (ref "U1") (pin "19") (pinfunction "VDD_19") (pintype "power_in"))
      (node (ref "U1") (pin "22") (pinfunction "VDDA_22") (pintype "power_in"))
      (node (ref "U1") (pin "28") (pinfunction "VDD_28") (pintype "power_in"))
      (node (ref "U1") (pin "50") (pinfunction "VDD_50") (pintype "power_in"))
      (node (ref "U1") (pin "6") (pinfunction "VBAT_6") (pintype "power_in"))
      (node (ref "U1") (pin "75") (pinfunction "VDD_75") (pintype "power_in"))
    )
    (net (code "83") (name "5V") (class "Default")
      (node (ref "C20") (pin "+") (pinfunction "+_+") (pintype "passive"))
      (node (ref "C23") (pin "1") (pinfunction "1_1") (pintype "passive"))
      (node (ref "C24") (pin "+") (pinfunction "+_+") (pintype "passive"))
      (node (ref "LeftHeader") (pin "2") (pinfunction "2_2") (pintype "passive"))
      (node (ref "LeftHeader") (pin "43") (pinfunction "43_43") (pintype "passive"))
      (node (ref "R6") (pin "2") (pinfunction "2_2") (pintype "passive"))
      (node (ref "U2") (pin "1") (pinfunction "IN_1") (pintype "passive"))
    )
    (net (code "84") (name "GND") (class "Default")
      (node (ref "C1") (pin "2") (pinfunction "2_2") (pintype "passive"))
      (node (ref "C10") (pin "-") (pinfunction "-_-") (pintype "passive"))
      (node (ref "C11") (pin "2") (pinfunction "2_2") (pintype "passive"))
      (node (ref "C12") (pin "2") (pinfunction "2_2") (pintype "passive"))
      (node (ref "C13") (pin "2") (pinfunction "2_2") (pintype "passive"))
      (node (ref "C14") (pin "2") (pinfunction "2_2") (pintype "passive"))
      (node (ref "C15") (pin "2") (pinfunction "2_2") (pintype "passive"))
      (node (ref "C16") (pin "2") (pinfunction "2_2") (pintype "passive"))
      (node (ref "C17") (pin "2") (pinfunction "2_2") (pintype "passive"))
      (node (ref "C18") (pin "-") (pinfunction "-_-") (pintype "passive"))
      (node (ref "C19") (pin "2") (pinfunction "2_2") (pintype "passive"))
      (node (ref "C2") (pin "2") (pinfunction "2_2") (pintype "passive"))
      (node (ref "C20") (pin "-") (pinfunction "-_-") (pintype "passive"))
      (node (ref "C21") (pin "-") (pinfunction "-_-") (pintype "passive"))
      (node (ref "C22") (pin "1") (pinfunction "1_1") (pintype "passive"))
      (node (ref "C23") (pin "2") (pinfunction "2_2") (pintype "passive"))
      (node (ref "C24") (pin "-") (pinfunction "-_-") (pintype "passive"))
      (node (ref "C25") (pin "2") (pinfunction "2_2") (pintype "passive"))
      (node (ref "C26") (pin "2") (pinfunction "2_2") (pintype "passive"))
      (node (ref "C27") (pin "1") (pinfunction "1_1") (pintype "passive"))
      (node (ref "C28") (pin "-") (pinfunction "-_-") (pintype "passive"))
      (node (ref "C3") (pin "1") (pinfunction "1_1") (pintype "passive"))
      (node (ref "C4") (pin "1") (pinfunction "1_1") (pintype "passive"))
      (node (ref "C5") (pin "2") (pinfunction "2_2") (pintype "passive"))
      (node (ref "C6") (pin "-") (pinfunction "-_-") (pintype "passive"))
      (node (ref "C7") (pin "2") (pinfunction "2_2") (pintype "passive"))
      (node (ref "C8") (pin "-") (pinfunction "-_-") (pintype "passive"))
      (node (ref "LED1") (pin "2") (pinfunction "C_2") (pintype "passive"))
      (node (ref "LED2") (pin "2") (pinfunction "C_2") (pintype "passive"))
      (node (ref "LED3") (pin "2") (pinfunction "C_2") (pintype "passive"))
      (node (ref "LED4") (pin "2") (pinfunction "C_2") (pintype "passive"))
      (node (ref "LED5") (pin "2") (pinfunction "C_2") (pintype "passive"))
      (node (ref "LED6") (pin "2") (pinfunction "C_2") (pintype "passive"))
      (node (ref "LeftHeader") (pin "1") (pinfunction "1_1") (pintype "passive"))
      (node (ref "LeftHeader") (pin "44") (pinfunction "44_44") (pintype "passive"))
      (node (ref "ProgrammingPort") (pin "10") (pinfunction "10_10") (pintype "passive"))
      (node (ref "ProgrammingPort") (pin "12") (pinfunction "12_12") (pintype "passive"))
      (node (ref "ProgrammingPort") (pin "14") (pinfunction "14_14") (pintype "passive"))
      (node (ref "ProgrammingPort") (pin "16") (pinfunction "16_16") (pintype "passive"))
      (node (ref "ProgrammingPort") (pin "18") (pinfunction "18_18") (pintype "passive"))
      (node (ref "ProgrammingPort") (pin "20") (pinfunction "20_20") (pintype "passive"))
      (node (ref "ProgrammingPort") (pin "3") (pinfunction "3_3") (pintype "passive"))
      (node (ref "ProgrammingPort") (pin "4") (pinfunction "4_4") (pintype "passive"))
      (node (ref "ProgrammingPort") (pin "5") (pinfunction "5_5") (pintype "passive"))
      (node (ref "ProgrammingPort") (pin "6") (pinfunction "6_6") (pintype "passive"))
      (node (ref "ProgrammingPort") (pin "8") (pinfunction "8_8") (pintype "passive"))
      (node (ref "R10") (pin "1") (pinfunction "1_1") (pintype "passive"))
      (node (ref "R12") (pin "1") (pinfunction "1_1") (pintype "passive"))
      (node (ref "RightHeader") (pin "1") (pinfunction "1_1") (pintype "passive"))
      (node (ref "RightHeader") (pin "44") (pinfunction "44_44") (pintype "passive"))
      (node (ref "S1") (pin "1") (pinfunction "1_1") (pintype "passive"))
      (node (ref "S1") (pin "3") (pinfunction "3_3") (pintype "passive"))
      (node (ref "U1") (pin "10") (pinfunction "VSS_10") (pintype "power_in"))
      (node (ref "U1") (pin "20") (pinfunction "VSSA_20") (pintype "power_in"))
      (node (ref "U1") (pin "27") (pinfunction "VSS_27") (pintype "power_in"))
      (node (ref "U1") (pin "74") (pinfunction "VSS_74") (pintype "power_in"))
      (node (ref "U1") (pin "99") (pinfunction "VSS_99") (pintype "power_in"))
      (node (ref "U2") (pin "2") (pinfunction "GND_2") (pintype "passive"))
    )
    (net (code "85") (name "Net-(C1-Pad1)") (class "Default")
      (node (ref "C1") (pin "1") (pinfunction "1_1") (pintype "passive"))
      (node (ref "R7") (pin "1") (pinfunction "1_1") (pintype "passive"))
      (node (ref "X1") (pin "2") (pinfunction "2_2") (pintype "passive"))
    )
    (net (code "86") (name "Net-(C2-Pad1)") (class "Default")
      (node (ref "C2") (pin "1") (pinfunction "1_1") (pintype "passive"))
      (node (ref "R8") (pin "1") (pinfunction "1_1") (pintype "passive"))
      (node (ref "X1") (pin "1") (pinfunction "1_1") (pintype "passive"))
    )
    (net (code "87") (name "Net-(LED1-A)") (class "Default")
      (node (ref "LED1") (pin "1") (pinfunction "A_1") (pintype "passive"))
      (node (ref "R1") (pin "1") (pinfunction "1_1") (pintype "passive"))
    )
    (net (code "88") (name "Net-(LED2-A)") (class "Default")
      (node (ref "LED2") (pin "1") (pinfunction "A_1") (pintype "passive"))
      (node (ref "R2") (pin "1") (pinfunction "1_1") (pintype "passive"))
    )
    (net (code "89") (name "Net-(LED3-A)") (class "Default")
      (node (ref "LED3") (pin "1") (pinfunction "A_1") (pintype "passive"))
      (node (ref "R3") (pin "1") (pinfunction "1_1") (pintype "passive"))
    )
    (net (code "90") (name "Net-(LED4-A)") (class "Default")
      (node (ref "LED4") (pin "1") (pinfunction "A_1") (pintype "passive"))
      (node (ref "R4") (pin "1") (pinfunction "1_1") (pintype "passive"))
    )
    (net (code "91") (name "Net-(LED5-A)") (class "Default")
      (node (ref "LED5") (pin "1") (pinfunction "A_1") (pintype "passive"))
      (node (ref "R5") (pin "1") (pinfunction "1_1") (pintype "passive"))
    )
    (net (code "92") (name "Net-(LED6-A)") (class "Default")
      (node (ref "LED6") (pin "1") (pinfunction "A_1") (pintype "passive"))
      (node (ref "R6") (pin "1") (pinfunction "1_1") (pintype "passive"))
    )
    (net (code "93") (name "Net-(U1A-PB2-BOOT1(PB2){slash}EVENTOUT)") (class "Default")
      (node (ref "R11") (pin "1") (pinfunction "1_1") (pintype "passive"))
      (node (ref "R12") (pin "2") (pinfunction "2_2") (pintype "passive"))
      (node (ref "U1") (pin "37") (pinfunction "PB2-BOOT1(PB2)/EVENTOUT_37") (pintype "bidirectional"))
    )
    (net (code "94") (name "Net-(U1D-BOOT0{slash}VPP)") (class "Default")
      (node (ref "R10") (pin "2") (pinfunction "2_2") (pintype "passive"))
      (node (ref "R9") (pin "1") (pinfunction "1_1") (pintype "passive"))
      (node (ref "U1") (pin "94") (pinfunction "BOOT0/VPP_94") (pintype "input"))
    )
    (net (code "95") (name "Net-(U1D-PH0-OSC_IN(PH0){slash}EVENTOUT{slash}OSC_IN)") (class "Default")
      (node (ref "R8") (pin "2") (pinfunction "2_2") (pintype "passive"))
      (node (ref "U1") (pin "12") (pinfunction "PH0-OSC_IN(PH0)/EVENTOUT/OSC_IN_12") (pintype "bidirectional"))
    )
    (net (code "96") (name "Net-(U1D-PH1-OSC_OUT(PH1){slash}EVENTOUT{slash}OSC_OUT)") (class "Default")
      (node (ref "R7") (pin "2") (pinfunction "2_2") (pintype "passive"))
      (node (ref "U1") (pin "13") (pinfunction "PH1-OSC_OUT(PH1)/EVENTOUT/OSC_OUT_13") (pintype "bidirectional"))
    )
    (net (code "97") (name "Net-(U1D-VCAP_1)") (class "Default")
      (node (ref "C3") (pin "2") (pinfunction "2_2") (pintype "passive"))
      (node (ref "U1") (pin "49") (pinfunction "VCAP_1_49") (pintype "power_in"))
    )
    (net (code "98") (name "Net-(U1D-VCAP_2)") (class "Default")
      (node (ref "C4") (pin "2") (pinfunction "2_2") (pintype "passive"))
      (node (ref "U1") (pin "73") (pinfunction "VCAP_2_73") (pintype "power_in"))
    )
    (net (code "99") (name "Net-(U1E-VREF+)") (class "Default")
      (node (ref "C5") (pin "1") (pinfunction "1_1") (pintype "passive"))
      (node (ref "C6") (pin "+") (pinfunction "+_+") (pintype "passive"))
      (node (ref "C7") (pin "1") (pinfunction "1_1") (pintype "passive"))
      (node (ref "RefSelect") (pin "2") (pinfunction "2_2") (pintype "passive"))
      (node (ref "U1") (pin "21") (pinfunction "VREF+_21") (pintype "power_in"))
    )
    (net (code "100") (name "unconnected-(ProgrammingPort-Pad11)") (class "Default")
      (node (ref "ProgrammingPort") (pin "11") (pinfunction "11_11") (pintype "passive+no_connect"))
    )
    (net (code "101") (name "unconnected-(ProgrammingPort-Pad17)") (class "Default")
      (node (ref "ProgrammingPort") (pin "17") (pinfunction "17_17") (pintype "passive+no_connect"))
    )
    (net (code "102") (name "unconnected-(ProgrammingPort-Pad19)") (class "Default")
      (node (ref "ProgrammingPort") (pin "19") (pinfunction "19_19") (pintype "passive+no_connect"))
    )
  )
)
